# GSM_Link_12_MCU.net
KiCad netlist of a schematic drawn in Altium Designer
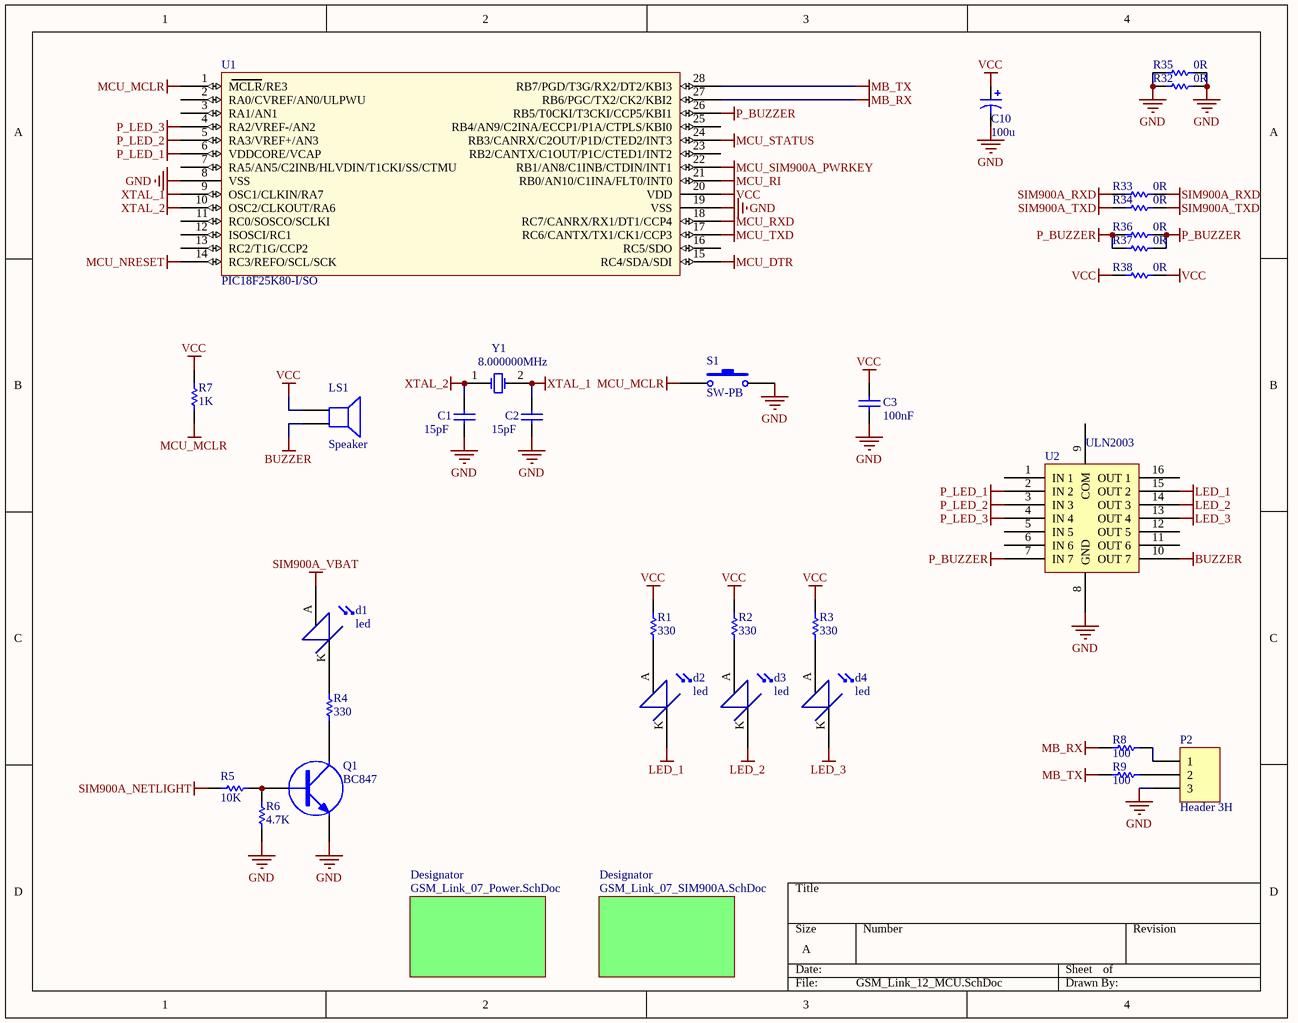
[diagram p0: GSM_Link_12_MCU.SchDoc]

(export (version "E")
  (design (tool "Eeschema 10.0.6"))
  (components
    (comp (ref "C1")
      (value "15pF")
      (footprint "0805_smd")
      (description "Capacitor")
      (fields (field (name "PUBLISHER") "Altium Limited"))
      (libsource (lib "Miscellaneous Devices") (part "Cap"))
    )
    (comp (ref "C2")
      (value "15pF")
      (footprint "0805_smd")
      (description "Capacitor")
      (fields (field (name "PUBLISHER") "Altium Limited"))
      (libsource (lib "Miscellaneous Devices") (part "Cap"))
    )
    (comp (ref "C3")
      (value "100nF")
      (footprint "0805_smd")
      (description "Capacitor")
      (fields (field (name "PUBLISHER") "Altium Limited"))
      (libsource (lib "Miscellaneous Devices") (part "Cap"))
    )
    (comp (ref "C10")
      (value "100u")
      (footprint "RB.1/.2_P")
      (description "Polarized Capacitor (Radial)")
      (fields (field (name "PUBLISHER") "Altium Limited"))
      (libsource (lib "Miscellaneous Devices") (part "Cap Pol1"))
    )
    (comp (ref "d1") (value "led") (footprint "0603_LED_SMD") (libsource (lib "SchLib377") (part "led")))
    (comp (ref "d2") (value "led") (footprint "0603_LED_SMD") (libsource (lib "SchLib377") (part "led")))
    (comp (ref "d3") (value "led") (footprint "0603_LED_SMD") (libsource (lib "SchLib377") (part "led")))
    (comp (ref "d4") (value "led") (footprint "0603_LED_SMD") (libsource (lib "SchLib377") (part "led")))
    (comp (ref "LS1")
      (value "Speaker")
      (footprint "BZ_KD")
      (description "Loudspeaker")
      (fields (field (name "PUBLISHER") "Altium Limited"))
      (libsource (lib "Miscellaneous Devices") (part "Speaker"))
    )
    (comp (ref "P2")
      (value "Header 3H")
      (footprint "CON3_XH")
      (description "Header, 3-Pin, Right Angle")
      (fields (field (name "PUBLISHER") "Altium Limited"))
      (libsource (lib "Miscellaneous Connectors") (part "Header 3H"))
    )
    (comp (ref "Q1") (value "BC847") (footprint "SOT23_SMD") (libsource (lib "Schlib75") (part "BC547")))
    (comp (ref "R1")
      (value "330")
      (footprint "0805_SMD")
      (description "Resistor")
      (fields (field (name "PUBLISHER") "Altium Limited"))
      (libsource (lib "Miscellaneous Devices") (part "Res1"))
    )
    (comp (ref "R2")
      (value "330")
      (footprint "0805_SMD")
      (description "Resistor")
      (fields (field (name "PUBLISHER") "Altium Limited"))
      (libsource (lib "Miscellaneous Devices") (part "Res1"))
    )
    (comp (ref "R3")
      (value "330")
      (footprint "0805_SMD")
      (description "Resistor")
      (fields (field (name "PUBLISHER") "Altium Limited"))
      (libsource (lib "Miscellaneous Devices") (part "Res1"))
    )
    (comp (ref "R4")
      (value "330")
      (footprint "0805_SMD")
      (description "Resistor")
      (fields (field (name "PUBLISHER") "Altium Limited"))
      (libsource (lib "Miscellaneous Devices") (part "Res1"))
    )
    (comp (ref "R5")
      (value "10K")
      (footprint "0805_SMD")
      (description "Resistor")
      (fields (field (name "PUBLISHER") "Altium Limited"))
      (libsource (lib "Miscellaneous Devices") (part "Res1"))
    )
    (comp (ref "R6")
      (value "4.7K")
      (footprint "0805_SMD")
      (description "Resistor")
      (fields (field (name "PUBLISHER") "Altium Limited"))
      (libsource (lib "Miscellaneous Devices") (part "Res1"))
    )
    (comp (ref "R7")
      (value "1K")
      (footprint "1206_SMD")
      (description "Resistor")
      (fields (field (name "PUBLISHER") "Altium Limited"))
      (libsource (lib "Miscellaneous Devices") (part "Res1"))
    )
    (comp (ref "R8")
      (value "100")
      (footprint "0805_SMD")
      (description "Resistor")
      (fields (field (name "PUBLISHER") "Altium Limited"))
      (libsource (lib "Miscellaneous Devices") (part "Res1"))
    )
    (comp (ref "R9")
      (value "100")
      (footprint "0805_SMD")
      (description "Resistor")
      (fields (field (name "PUBLISHER") "Altium Limited"))
      (libsource (lib "Miscellaneous Devices") (part "Res1"))
    )
    (comp (ref "R32")
      (value "0R")
      (footprint "1206_SMD")
      (description "Resistor")
      (fields (field (name "PUBLISHER") "Altium Limited"))
      (libsource (lib "Miscellaneous Devices") (part "Res1"))
    )
    (comp (ref "R33")
      (value "0R")
      (footprint "1206_SMD")
      (description "Resistor")
      (fields (field (name "PUBLISHER") "Altium Limited"))
      (libsource (lib "Miscellaneous Devices") (part "Res1"))
    )
    (comp (ref "R34")
      (value "0R")
      (footprint "1206_SMD")
      (description "Resistor")
      (fields (field (name "PUBLISHER") "Altium Limited"))
      (libsource (lib "Miscellaneous Devices") (part "Res1"))
    )
    (comp (ref "R35")
      (value "0R")
      (footprint "1206_SMD")
      (description "Resistor")
      (fields (field (name "PUBLISHER") "Altium Limited"))
      (libsource (lib "Miscellaneous Devices") (part "Res1"))
    )
    (comp (ref "R36")
      (value "0R")
      (footprint "1206_SMD")
      (description "Resistor")
      (fields (field (name "PUBLISHER") "Altium Limited"))
      (libsource (lib "Miscellaneous Devices") (part "Res1"))
    )
    (comp (ref "R37")
      (value "0R")
      (footprint "2010_SMD")
      (description "Resistor")
      (fields (field (name "PUBLISHER") "Altium Limited"))
      (libsource (lib "Miscellaneous Devices") (part "Res1"))
    )
    (comp (ref "R38")
      (value "0R")
      (footprint "1206_SMD")
      (description "Resistor")
      (fields (field (name "PUBLISHER") "Altium Limited"))
      (libsource (lib "Miscellaneous Devices") (part "Res1"))
    )
    (comp (ref "S1")
      (value "SW-PB")
      (footprint "switch3_smd")
      (description "Switch")
      (fields (field (name "PUBLISHER") "Altium Limited"))
      (libsource (lib "Miscellaneous Devices") (part "SW-PB"))
    )
    (comp (ref "U1")
      (value "PIC18F25K80-I/SO")
      (footprint "SOIC28_SMD")
      (libsource (lib "BNB_Altium_LIB_002") (part "PIC18F25K80-I/SO"))
    )
    (comp (ref "U2") (value "ULN2003") (footprint "SO-16_smd") (libsource (lib "SchLib260") (part "ULN2003")))
    (comp (ref "Y1")
      (value "8.000000MHz")
      (footprint "rad-0.2")
      (description "Crystal Oscillator")
      (fields (field (name "PUBLISHER") "Altium Limited"))
      (libsource (lib "Miscellaneous Devices") (part "XTAL"))
    )
  )
  (nets
    (net (code "1") (name "BUZZER") (class "Default")
      (node (ref "LS1") (pin "2") (pinfunction "2_2") (pintype "passive"))
      (node (ref "U2") (pin "10") (pinfunction "OUT_7_10") (pintype "passive"))
    )
    (net (code "2") (name "GND") (class "Default")
      (node (ref "C1") (pin "1") (pinfunction "1_1") (pintype "passive"))
      (node (ref "C10") (pin "2") (pinfunction "2_2") (pintype "passive"))
      (node (ref "C2") (pin "1") (pinfunction "1_1") (pintype "passive"))
      (node (ref "C3") (pin "1") (pinfunction "1_1") (pintype "passive"))
      (node (ref "P2") (pin "3") (pinfunction "3_3") (pintype "passive"))
      (node (ref "Q1") (pin "2") (pinfunction "E_2") (pintype "passive"))
      (node (ref "R32") (pin "1") (pinfunction "1_1") (pintype "passive"))
      (node (ref "R32") (pin "2") (pinfunction "2_2") (pintype "passive"))
      (node (ref "R35") (pin "1") (pinfunction "1_1") (pintype "passive"))
      (node (ref "R35") (pin "2") (pinfunction "2_2") (pintype "passive"))
      (node (ref "R6") (pin "1") (pinfunction "1_1") (pintype "passive"))
      (node (ref "S1") (pin "2") (pinfunction "2_2") (pintype "passive"))
      (node (ref "U1") (pin "19") (pinfunction "VSS_19") (pintype "power_in"))
      (node (ref "U1") (pin "8") (pinfunction "VSS_8") (pintype "power_in"))
      (node (ref "U2") (pin "8") (pinfunction "GND_8") (pintype "passive"))
    )
    (net (code "3") (name "LED_1") (class "Default")
      (node (ref "U2") (pin "15") (pinfunction "OUT_2_15") (pintype "passive"))
      (node (ref "d2") (pin "K") (pintype "passive"))
    )
    (net (code "4") (name "LED_2") (class "Default")
      (node (ref "U2") (pin "14") (pinfunction "OUT_3_14") (pintype "passive"))
      (node (ref "d3") (pin "K") (pintype "passive"))
    )
    (net (code "5") (name "LED_3") (class "Default")
      (node (ref "U2") (pin "13") (pinfunction "OUT_4_13") (pintype "passive"))
      (node (ref "d4") (pin "K") (pintype "passive"))
    )
    (net (code "6") (name "MB_RX") (class "Default")
      (node (ref "R8") (pin "1") (pinfunction "1_1") (pintype "passive"))
      (node (ref "U1") (pin "27") (pinfunction "RB6/PGC/TX2/CK2/KBI2_27") (pintype "bidirectional"))
    )
    (net (code "7") (name "MB_TX") (class "Default")
      (node (ref "R9") (pin "1") (pinfunction "1_1") (pintype "passive"))
      (node (ref "U1") (pin "28") (pinfunction "RB7/PGD/T3G/RX2/DT2/KBI3_28") (pintype "bidirectional"))
    )
    (net (code "8") (name "MCU_DTR") (class "Default")
      (node (ref "U1") (pin "15") (pinfunction "RC4/SDA/SDI_15") (pintype "bidirectional"))
    )
    (net (code "9") (name "MCU_MCLR") (class "Default")
      (node (ref "R7") (pin "2") (pinfunction "2_2") (pintype "passive"))
      (node (ref "S1") (pin "1") (pinfunction "1_1") (pintype "passive"))
      (node (ref "U1") (pin "1") (pinfunction "MCLR/RE3_1") (pintype "bidirectional"))
    )
    (net (code "10") (name "MCU_NRESET") (class "Default")
      (node (ref "U1") (pin "14") (pinfunction "RC3/REFO/SCL/SCK_14") (pintype "bidirectional"))
    )
    (net (code "11") (name "MCU_RI") (class "Default")
      (node (ref "U1") (pin "21") (pinfunction "RB0/AN10/C1INA/FLT0/INT0_21") (pintype "bidirectional"))
    )
    (net (code "12") (name "MCU_RXD") (class "Default")
      (node (ref "U1") (pin "18") (pinfunction "RC7/CANRX/RX1/DT1/CCP4_18") (pintype "bidirectional"))
    )
    (net (code "13") (name "MCU_SIM900A_PWRKEY") (class "Default")
      (node (ref "U1") (pin "22") (pinfunction "RB1/AN8/C1INB/CTDIN/INT1_22") (pintype "bidirectional"))
    )
    (net (code "14") (name "MCU_STATUS") (class "Default")
      (node (ref "U1") (pin "24") (pinfunction "RB3/CANRX/C2OUT/P1D/CTED2/INT3_24") (pintype "bidirectional"))
    )
    (net (code "15") (name "MCU_TXD") (class "Default")
      (node (ref "U1") (pin "17") (pinfunction "RC6/CANTX/TX1/CK1/CCP3_17") (pintype "bidirectional"))
    )
    (net (code "16") (name "Net-(P2-Pad1)") (class "Default")
      (node (ref "P2") (pin "1") (pinfunction "1_1") (pintype "passive"))
      (node (ref "R8") (pin "2") (pinfunction "2_2") (pintype "passive"))
    )
    (net (code "17") (name "Net-(P2-Pad2)") (class "Default")
      (node (ref "P2") (pin "2") (pinfunction "2_2") (pintype "passive"))
      (node (ref "R9") (pin "2") (pinfunction "2_2") (pintype "passive"))
    )
    (net (code "18") (name "Net-(Q1-B)") (class "Default")
      (node (ref "Q1") (pin "1") (pinfunction "B_1") (pintype "passive"))
      (node (ref "R5") (pin "1") (pinfunction "1_1") (pintype "passive"))
      (node (ref "R6") (pin "2") (pinfunction "2_2") (pintype "passive"))
    )
    (net (code "19") (name "Net-(Q1-C)") (class "Default")
      (node (ref "Q1") (pin "3") (pinfunction "C_3") (pintype "passive"))
      (node (ref "R4") (pin "2") (pinfunction "2_2") (pintype "passive"))
    )
    (net (code "20") (name "Net-(R1-Pad2)") (class "Default")
      (node (ref "R1") (pin "2") (pinfunction "2_2") (pintype "passive"))
      (node (ref "d2") (pin "A") (pintype "passive"))
    )
    (net (code "21") (name "Net-(R2-Pad2)") (class "Default")
      (node (ref "R2") (pin "2") (pinfunction "2_2") (pintype "passive"))
      (node (ref "d3") (pin "A") (pintype "passive"))
    )
    (net (code "22") (name "Net-(R3-Pad2)") (class "Default")
      (node (ref "R3") (pin "2") (pinfunction "2_2") (pintype "passive"))
      (node (ref "d4") (pin "A") (pintype "passive"))
    )
    (net (code "23") (name "Net-(R4-Pad1)") (class "Default")
      (node (ref "R4") (pin "1") (pinfunction "1_1") (pintype "passive"))
      (node (ref "d1") (pin "K") (pintype "passive"))
    )
    (net (code "24") (name "P_BUZZER") (class "Default")
      (node (ref "R36") (pin "1") (pinfunction "1_1") (pintype "passive"))
      (node (ref "R36") (pin "2") (pinfunction "2_2") (pintype "passive"))
      (node (ref "R37") (pin "1") (pinfunction "1_1") (pintype "passive"))
      (node (ref "R37") (pin "2") (pinfunction "2_2") (pintype "passive"))
      (node (ref "U1") (pin "26") (pinfunction "RB5/T0CKI/T3CKI/CCP5/KBI1_26") (pintype "bidirectional"))
      (node (ref "U2") (pin "7") (pinfunction "IN_7_7") (pintype "passive"))
    )
    (net (code "25") (name "P_LED_1") (class "Default")
      (node (ref "U1") (pin "6") (pinfunction "VDDCORE/VCAP_6") (pintype "bidirectional"))
      (node (ref "U2") (pin "2") (pinfunction "IN_2_2") (pintype "passive"))
    )
    (net (code "26") (name "P_LED_2") (class "Default")
      (node (ref "U1") (pin "5") (pinfunction "RA3/VREF+/AN3_5") (pintype "bidirectional"))
      (node (ref "U2") (pin "3") (pinfunction "IN_3_3") (pintype "passive"))
    )
    (net (code "27") (name "P_LED_3") (class "Default")
      (node (ref "U1") (pin "4") (pinfunction "RA2/VREF-/AN2_4") (pintype "bidirectional"))
      (node (ref "U2") (pin "4") (pinfunction "IN_4_4") (pintype "passive"))
    )
    (net (code "28") (name "SIM900A_NETLIGHT") (class "Default")
      (node (ref "R5") (pin "2") (pinfunction "2_2") (pintype "passive"))
    )
    (net (code "29") (name "SIM900A_RXD") (class "Default")
      (node (ref "R33") (pin "1") (pinfunction "1_1") (pintype "passive"))
      (node (ref "R33") (pin "2") (pinfunction "2_2") (pintype "passive"))
    )
    (net (code "30") (name "SIM900A_TXD") (class "Default")
      (node (ref "R34") (pin "1") (pinfunction "1_1") (pintype "passive"))
      (node (ref "R34") (pin "2") (pinfunction "2_2") (pintype "passive"))
    )
    (net (code "31") (name "SIM900A_VBAT") (class "Default") (node (ref "d1") (pin "A") (pintype "passive")))
    (net (code "32") (name "VCC") (class "Default")
      (node (ref "C10") (pin "1") (pinfunction "1_1") (pintype "passive"))
      (node (ref "C3") (pin "2") (pinfunction "2_2") (pintype "passive"))
      (node (ref "LS1") (pin "1") (pinfunction "1_1") (pintype "passive"))
      (node (ref "R1") (pin "1") (pinfunction "1_1") (pintype "passive"))
      (node (ref "R2") (pin "1") (pinfunction "1_1") (pintype "passive"))
      (node (ref "R3") (pin "1") (pinfunction "1_1") (pintype "passive"))
      (node (ref "R38") (pin "1") (pinfunction "1_1") (pintype "passive"))
      (node (ref "R38") (pin "2") (pinfunction "2_2") (pintype "passive"))
      (node (ref "R7") (pin "1") (pinfunction "1_1") (pintype "passive"))
      (node (ref "U1") (pin "20") (pinfunction "VDD_20") (pintype "power_in"))
    )
    (net (code "33") (name "XTAL_1") (class "Default")
      (node (ref "C2") (pin "2") (pinfunction "2_2") (pintype "passive"))
      (node (ref "U1") (pin "9") (pinfunction "OSC1/CLKIN/RA7_9") (pintype "bidirectional"))
      (node (ref "Y1") (pin "2") (pinfunction "OSC2_2") (pintype "passive"))
    )
    (net (code "34") (name "XTAL_2") (class "Default")
      (node (ref "C1") (pin "2") (pinfunction "2_2") (pintype "passive"))
      (node (ref "U1") (pin "10") (pinfunction "OSC2/CLKOUT/RA6_10") (pintype "bidirectional"))
      (node (ref "Y1") (pin "1") (pinfunction "OSC1_1") (pintype "passive"))
    )
    (net (code "35") (name "unconnected-(U1-ISOSCI{slash}RC1-Pad12)") (class "Default")
      (node (ref "U1") (pin "12") (pinfunction "ISOSCI/RC1_12") (pintype "bidirectional"))
    )
    (net (code "36") (name "unconnected-(U1-RA0{slash}CVREF{slash}AN0{slash}ULPWU-Pad2)") (class "Default")
      (node (ref "U1") (pin "2") (pinfunction "RA0/CVREF/AN0/ULPWU_2") (pintype "bidirectional"))
    )
    (net (code "37") (name "unconnected-(U1-RA1{slash}AN1-Pad3)") (class "Default")
      (node (ref "U1") (pin "3") (pinfunction "RA1/AN1_3") (pintype "bidirectional"))
    )
    (net (code "38") (name "unconnected-(U1-RA5{slash}AN5{slash}C2INB{slash}HLVDIN{slash}T1CKI{slash}SS{slash}CTMU-Pad7)") (class "Default")
      (node (ref "U1") (pin "7") (pinfunction "RA5/AN5/C2INB/HLVDIN/T1CKI/SS/CTMU_7") (pintype "bidirectional"))
    )
    (net (code "39") (name "unconnected-(U1-RB2{slash}CANTX{slash}C1OUT{slash}P1C{slash}CTED1{slash}INT2-Pad23)") (class "Default")
      (node (ref "U1") (pin "23") (pinfunction "RB2/CANTX/C1OUT/P1C/CTED1/INT2_23") (pintype "bidirectional"))
    )
    (net (code "40") (name "unconnected-(U1-RB4{slash}AN9{slash}C2INA{slash}ECCP1{slash}P1A{slash}CTPLS{slash}KBI0-Pad25)") (class "Default")
      (node (ref "U1") (pin "25") (pinfunction "RB4/AN9/C2INA/ECCP1/P1A/CTPLS/KBI0_25") (pintype "bidirectional"))
    )
    (net (code "41") (name "unconnected-(U1-RC0{slash}SOSCO{slash}SCLKI-Pad11)") (class "Default")
      (node (ref "U1") (pin "11") (pinfunction "RC0/SOSCO/SCLKI_11") (pintype "bidirectional"))
    )
    (net (code "42") (name "unconnected-(U1-RC2{slash}T1G{slash}CCP2-Pad13)") (class "Default")
      (node (ref "U1") (pin "13") (pinfunction "RC2/T1G/CCP2_13") (pintype "bidirectional"))
    )
    (net (code "43") (name "unconnected-(U1-RC5{slash}SDO-Pad16)") (class "Default")
      (node (ref "U1") (pin "16") (pinfunction "RC5/SDO_16") (pintype "bidirectional"))
    )
    (net (code "44") (name "unconnected-(U2-COM-Pad9)") (class "Default")
      (node (ref "U2") (pin "9") (pinfunction "COM_9") (pintype "passive"))
    )
    (net (code "45") (name "unconnected-(U2-IN_1-Pad1)") (class "Default")
      (node (ref "U2") (pin "1") (pinfunction "IN_1_1") (pintype "passive"))
    )
    (net (code "46") (name "unconnected-(U2-IN_5-Pad5)") (class "Default")
      (node (ref "U2") (pin "5") (pinfunction "IN_5_5") (pintype "passive"))
    )
    (net (code "47") (name "unconnected-(U2-IN_6-Pad6)") (class "Default")
      (node (ref "U2") (pin "6") (pinfunction "IN_6_6") (pintype "passive"))
    )
    (net (code "48") (name "unconnected-(U2-OUT_1-Pad16)") (class "Default")
      (node (ref "U2") (pin "16") (pinfunction "OUT_1_16") (pintype "passive"))
    )
    (net (code "49") (name "unconnected-(U2-OUT_5-Pad12)") (class "Default")
      (node (ref "U2") (pin "12") (pinfunction "OUT_5_12") (pintype "passive"))
    )
    (net (code "50") (name "unconnected-(U2-OUT_6-Pad11)") (class "Default")
      (node (ref "U2") (pin "11") (pinfunction "OUT_6_11") (pintype "passive"))
    )
  )
)
